# cloudy1.net
KiCad netlist of a schematic drawn in EAGLE
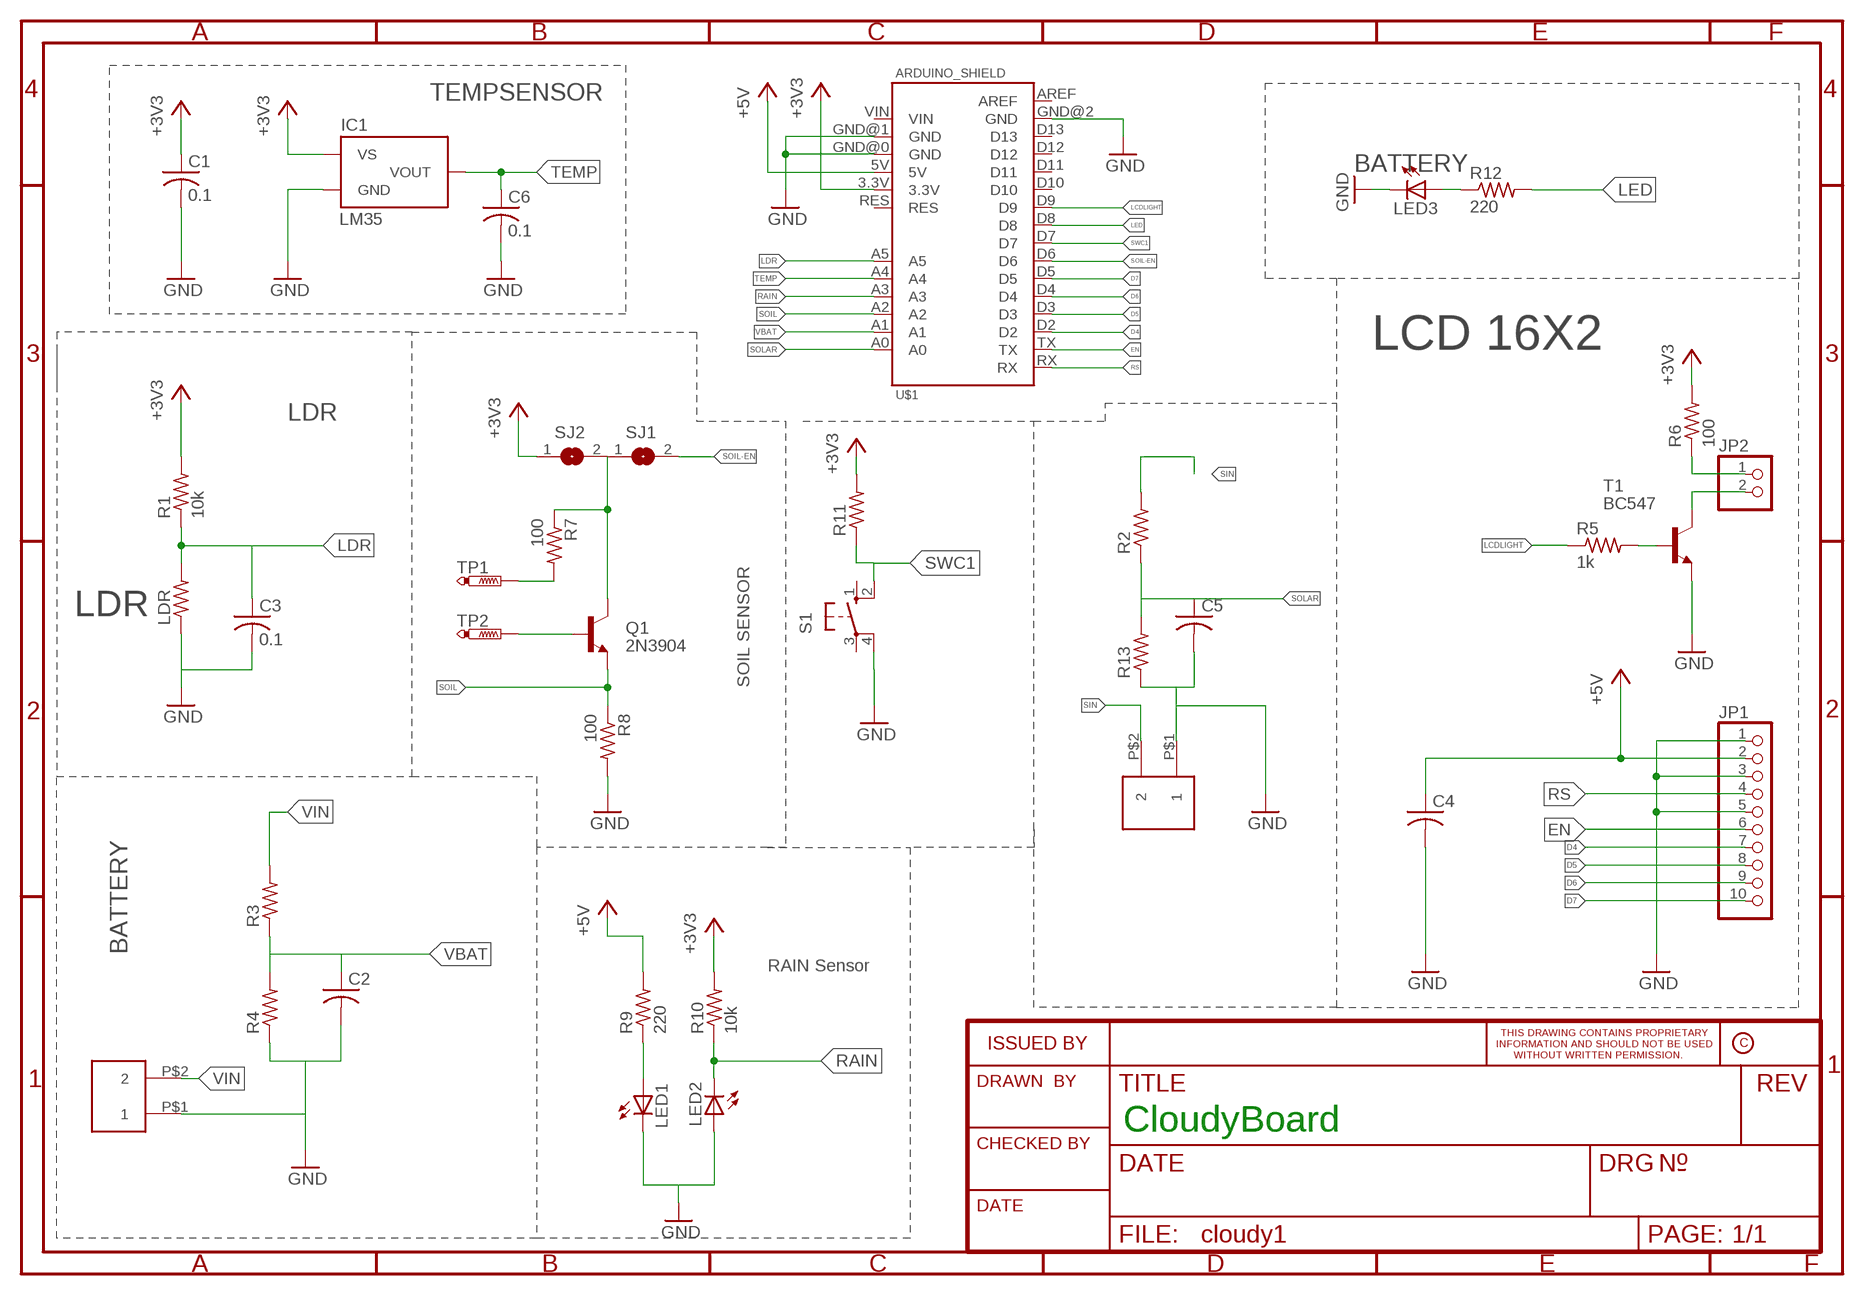
[diagram p0: schematic, sheet 1]

(export (version "E")
  (design (tool "Eeschema 10.0.6"))
  (components
    (comp (ref "C1")
      (value "0.1")
      (footprint "eagle-import:C0805")
      (libsource (lib "eagle-import") (part "C-USC0805"))
    )
    (comp (ref "C2")
      (value "C-USC0805")
      (footprint "eagle-import:C0805")
      (libsource (lib "eagle-import") (part "C-USC0805"))
    )
    (comp (ref "C3")
      (value "0.1")
      (footprint "eagle-import:C0805")
      (libsource (lib "eagle-import") (part "C-USC0805"))
    )
    (comp (ref "C4")
      (value "C-USC0805")
      (footprint "eagle-import:C0805")
      (libsource (lib "eagle-import") (part "C-USC0805"))
    )
    (comp (ref "C5")
      (value "C-USC0805")
      (footprint "eagle-import:C0805")
      (libsource (lib "eagle-import") (part "C-USC0805"))
    )
    (comp (ref "C6")
      (value "0.1")
      (footprint "eagle-import:C0805")
      (libsource (lib "eagle-import") (part "C-USC0805"))
    )
    (comp (ref "IC1")
      (value "LM35")
      (footprint "eagle-import:TO92")
      (libsource (lib "eagle-import") (part "LM35"))
    )
    (comp (ref "JP1")
      (value "PINHD-1X10")
      (footprint "eagle-import:1X10")
      (libsource (lib "eagle-import") (part "PINHD-1X10"))
    )
    (comp (ref "JP2")
      (value "PINHD-1X2")
      (footprint "eagle-import:1X02")
      (libsource (lib "eagle-import") (part "PINHD-1X2"))
    )
    (comp (ref "LDR")
      (value "R-US_0204/5")
      (footprint "eagle-import:0204_5")
      (libsource (lib "eagle-import") (part "R-US_0204/5"))
    )
    (comp (ref "LED1")
      (value "LED5MM")
      (footprint "eagle-import:LED5MM")
      (libsource (lib "eagle-import") (part "LED5MM"))
    )
    (comp (ref "LED2")
      (value "LED5MM")
      (footprint "eagle-import:LED5MM")
      (libsource (lib "eagle-import") (part "LED5MM"))
    )
    (comp (ref "LED3")
      (value "LED5MM")
      (footprint "eagle-import:LED5MM")
      (libsource (lib "eagle-import") (part "LED5MM"))
    )
    (comp (ref "Q1")
      (value "2N3904")
      (footprint "eagle-import:TO92")
      (libsource (lib "eagle-import") (part "2N3904"))
    )
    (comp (ref "R1")
      (value "10k")
      (footprint "eagle-import:0204_7")
      (libsource (lib "eagle-import") (part "R-US_0204/7"))
    )
    (comp (ref "R2")
      (value "R-US_0204/7")
      (footprint "eagle-import:0204_7")
      (libsource (lib "eagle-import") (part "R-US_0204/7"))
    )
    (comp (ref "R3")
      (value "R-US_0204/7")
      (footprint "eagle-import:0204_7")
      (libsource (lib "eagle-import") (part "R-US_0204/7"))
    )
    (comp (ref "R4")
      (value "R-US_0204/7")
      (footprint "eagle-import:0204_7")
      (libsource (lib "eagle-import") (part "R-US_0204/7"))
    )
    (comp (ref "R5")
      (value "1k")
      (footprint "eagle-import:0204_7")
      (libsource (lib "eagle-import") (part "R-US_0204/7"))
    )
    (comp (ref "R6")
      (value "100")
      (footprint "eagle-import:0204_7")
      (libsource (lib "eagle-import") (part "R-US_0204/7"))
    )
    (comp (ref "R7")
      (value "100")
      (footprint "eagle-import:R0805")
      (libsource (lib "eagle-import") (part "R-US_R0805"))
    )
    (comp (ref "R8")
      (value "100")
      (footprint "eagle-import:R0805")
      (libsource (lib "eagle-import") (part "R-US_R0805"))
    )
    (comp (ref "R9")
      (value "220")
      (footprint "eagle-import:0204_7")
      (libsource (lib "eagle-import") (part "R-US_0204/7"))
    )
    (comp (ref "R10")
      (value "10k")
      (footprint "eagle-import:0204_7")
      (libsource (lib "eagle-import") (part "R-US_0204/7"))
    )
    (comp (ref "R11")
      (value "R-US_0207/10")
      (footprint "eagle-import:0207_10")
      (libsource (lib "eagle-import") (part "R-US_0207/10"))
    )
    (comp (ref "R12")
      (value "220")
      (footprint "eagle-import:0204_7")
      (libsource (lib "eagle-import") (part "R-US_0204/7"))
    )
    (comp (ref "R13")
      (value "R-US_0204/7")
      (footprint "eagle-import:0204_7")
      (libsource (lib "eagle-import") (part "R-US_0204/7"))
    )
    (comp (ref "S1")
      (value "10-XX")
      (footprint "eagle-import:B3F-10XX")
      (libsource (lib "eagle-import") (part "10-XX"))
    )
    (comp (ref "SJ1") (value "SJ") (footprint "eagle-import:SJ") (libsource (lib "eagle-import") (part "SJ")))
    (comp (ref "SJ2") (value "SJ") (footprint "eagle-import:SJ") (libsource (lib "eagle-import") (part "SJ")))
    (comp (ref "T1")
      (value "BC547")
      (footprint "eagle-import:TO92")
      (libsource (lib "eagle-import") (part "BC547"))
    )
    (comp (ref "TP1")
      (value "PTR1TP19SQ")
      (footprint "eagle-import:TP19SQ")
      (libsource (lib "eagle-import") (part "PTR1TP19SQ"))
    )
    (comp (ref "TP2")
      (value "PTR1TP19SQ")
      (footprint "eagle-import:TP19SQ")
      (libsource (lib "eagle-import") (part "PTR1TP19SQ"))
    )
    (comp (ref "U$1")
      (value "ARDUINO_SHIELD")
      (footprint "eagle-import:ARDUINO_SHIELD")
      (libsource (lib "eagle-import") (part "ARDUINO_SHIELD"))
    )
    (comp (ref "U$2")
      (value "POWER_TERMINAL")
      (footprint "eagle-import:POWER_TERMINAL_2")
      (libsource (lib "eagle-import") (part "POWER_TERMINAL"))
    )
    (comp (ref "U$3")
      (value "POWER_TERMINAL")
      (footprint "eagle-import:POWER_TERMINAL_2")
      (libsource (lib "eagle-import") (part "POWER_TERMINAL"))
    )
  )
  (nets
    (net (code "1") (name "+3V3") (class "Default")
      (node (ref "C1") (pin "1") (pinfunction "1_1") (pintype "passive"))
      (node (ref "IC1") (pin "VS") (pinfunction "VS_VS") (pintype "passive"))
      (node (ref "R1") (pin "2") (pinfunction "2_2") (pintype "passive"))
      (node (ref "R10") (pin "2") (pinfunction "2_2") (pintype "passive"))
      (node (ref "R11") (pin "2") (pinfunction "2_2") (pintype "passive"))
      (node (ref "R6") (pin "2") (pinfunction "2_2") (pintype "passive"))
      (node (ref "SJ2") (pin "1") (pinfunction "1_1") (pintype "passive"))
      (node (ref "U$1") (pin "3.3V") (pinfunction "3.3V_3.3V") (pintype "passive"))
    )
    (net (code "2") (name "+5V") (class "Default")
      (node (ref "C4") (pin "1") (pinfunction "1_1") (pintype "passive"))
      (node (ref "JP1") (pin "2") (pinfunction "2_2") (pintype "passive"))
      (node (ref "R9") (pin "2") (pinfunction "2_2") (pintype "passive"))
      (node (ref "U$1") (pin "5V") (pinfunction "5V_5V") (pintype "passive"))
    )
    (net (code "3") (name "D4") (class "Default")
      (node (ref "JP1") (pin "7") (pinfunction "7_7") (pintype "passive"))
      (node (ref "U$1") (pin "D2") (pinfunction "D2_D2") (pintype "passive"))
    )
    (net (code "4") (name "D5") (class "Default")
      (node (ref "JP1") (pin "8") (pinfunction "8_8") (pintype "passive"))
      (node (ref "U$1") (pin "D3") (pinfunction "D3_D3") (pintype "passive"))
    )
    (net (code "5") (name "D6") (class "Default")
      (node (ref "JP1") (pin "9") (pinfunction "9_9") (pintype "passive"))
      (node (ref "U$1") (pin "D4") (pinfunction "D4_D4") (pintype "passive"))
    )
    (net (code "6") (name "D7") (class "Default")
      (node (ref "JP1") (pin "10") (pinfunction "10_10") (pintype "passive"))
      (node (ref "U$1") (pin "D5") (pinfunction "D5_D5") (pintype "passive"))
    )
    (net (code "7") (name "EN") (class "Default")
      (node (ref "JP1") (pin "6") (pinfunction "6_6") (pintype "passive"))
      (node (ref "U$1") (pin "TX") (pinfunction "TX_TX") (pintype "passive"))
    )
    (net (code "8") (name "GND") (class "Default")
      (node (ref "C1") (pin "2") (pinfunction "2_2") (pintype "passive"))
      (node (ref "C2") (pin "2") (pinfunction "2_2") (pintype "passive"))
      (node (ref "C3") (pin "2") (pinfunction "2_2") (pintype "passive"))
      (node (ref "C4") (pin "2") (pinfunction "2_2") (pintype "passive"))
      (node (ref "C5") (pin "2") (pinfunction "2_2") (pintype "passive"))
      (node (ref "C6") (pin "2") (pinfunction "2_2") (pintype "passive"))
      (node (ref "IC1") (pin "GND") (pinfunction "GND_GND") (pintype "passive"))
      (node (ref "JP1") (pin "1") (pinfunction "1_1") (pintype "passive"))
      (node (ref "JP1") (pin "3") (pinfunction "3_3") (pintype "passive"))
      (node (ref "JP1") (pin "5") (pinfunction "5_5") (pintype "passive"))
      (node (ref "LDR") (pin "1") (pinfunction "1_1") (pintype "passive"))
      (node (ref "LED1") (pin "K") (pinfunction "C_K") (pintype "passive"))
      (node (ref "LED2") (pin "A") (pinfunction "A_A") (pintype "passive"))
      (node (ref "LED3") (pin "K") (pinfunction "C_K") (pintype "passive"))
      (node (ref "R13") (pin "1") (pinfunction "1_1") (pintype "passive"))
      (node (ref "R4") (pin "1") (pinfunction "1_1") (pintype "passive"))
      (node (ref "R8") (pin "2") (pinfunction "2_2") (pintype "passive"))
      (node (ref "S1") (pin "4") (pinfunction "P1_4") (pintype "passive"))
      (node (ref "T1") (pin "1") (pinfunction "E_1") (pintype "passive"))
      (node (ref "U$1") (pin "GND@0") (pinfunction "GND_GND@0") (pintype "passive"))
      (node (ref "U$1") (pin "GND@1") (pinfunction "GND_GND@1") (pintype "passive"))
      (node (ref "U$1") (pin "GND@2") (pinfunction "GND_GND@2") (pintype "passive"))
      (node (ref "U$2") (pin "P$1") (pinfunction "1_P$1") (pintype "passive"))
      (node (ref "U$3") (pin "P$1") (pinfunction "1_P$1") (pintype "passive"))
    )
    (net (code "9") (name "LCDLIGHT") (class "Default")
      (node (ref "R5") (pin "1") (pinfunction "1_1") (pintype "passive"))
      (node (ref "U$1") (pin "D9") (pinfunction "D9_D9") (pintype "passive"))
    )
    (net (code "10") (name "LDR") (class "Default")
      (node (ref "C3") (pin "1") (pinfunction "1_1") (pintype "passive"))
      (node (ref "LDR") (pin "2") (pinfunction "2_2") (pintype "passive"))
      (node (ref "R1") (pin "1") (pinfunction "1_1") (pintype "passive"))
      (node (ref "U$1") (pin "A5") (pinfunction "A5_A5") (pintype "passive"))
    )
    (net (code "11") (name "LED") (class "Default")
      (node (ref "R12") (pin "2") (pinfunction "2_2") (pintype "passive"))
      (node (ref "U$1") (pin "D8") (pinfunction "D8_D8") (pintype "passive"))
    )
    (net (code "12") (name "Net-(JP2-Pad1)") (class "Default")
      (node (ref "JP2") (pin "1") (pinfunction "1_1") (pintype "passive"))
      (node (ref "R6") (pin "1") (pinfunction "1_1") (pintype "passive"))
    )
    (net (code "13") (name "Net-(LED1-PadA)") (class "Default")
      (node (ref "LED1") (pin "A") (pinfunction "A_A") (pintype "passive"))
      (node (ref "R9") (pin "1") (pinfunction "1_1") (pintype "passive"))
    )
    (net (code "14") (name "Net-(LED3-PadA)") (class "Default")
      (node (ref "LED3") (pin "A") (pinfunction "A_A") (pintype "passive"))
      (node (ref "R12") (pin "1") (pinfunction "1_1") (pintype "passive"))
    )
    (net (code "15") (name "Net-(Q1-B)") (class "Default")
      (node (ref "Q1") (pin "2") (pinfunction "B_2") (pintype "passive"))
      (node (ref "TP2") (pin "TP") (pinfunction "TP_TP") (pintype "input"))
    )
    (net (code "16") (name "Net-(Q1-C)") (class "Default")
      (node (ref "Q1") (pin "1") (pinfunction "C_1") (pintype "passive"))
      (node (ref "R7") (pin "1") (pinfunction "1_1") (pintype "passive"))
      (node (ref "SJ1") (pin "1") (pinfunction "1_1") (pintype "passive"))
      (node (ref "SJ2") (pin "2") (pinfunction "2_2") (pintype "passive"))
    )
    (net (code "17") (name "Net-(R7-Pad2)") (class "Default")
      (node (ref "R7") (pin "2") (pinfunction "2_2") (pintype "passive"))
      (node (ref "TP1") (pin "TP") (pinfunction "TP_TP") (pintype "input"))
    )
    (net (code "18") (name "Net-(T1-B)") (class "Default")
      (node (ref "R5") (pin "2") (pinfunction "2_2") (pintype "passive"))
      (node (ref "T1") (pin "2") (pinfunction "B_2") (pintype "passive"))
    )
    (net (code "19") (name "Net-(T1-C)") (class "Default")
      (node (ref "JP2") (pin "2") (pinfunction "2_2") (pintype "passive"))
      (node (ref "T1") (pin "3") (pinfunction "C_3") (pintype "passive"))
    )
    (net (code "20") (name "RAIN") (class "Default")
      (node (ref "LED2") (pin "K") (pinfunction "C_K") (pintype "passive"))
      (node (ref "R10") (pin "1") (pinfunction "1_1") (pintype "passive"))
      (node (ref "U$1") (pin "A3") (pinfunction "A3_A3") (pintype "passive"))
    )
    (net (code "21") (name "RS") (class "Default")
      (node (ref "JP1") (pin "4") (pinfunction "4_4") (pintype "passive"))
      (node (ref "U$1") (pin "RX") (pinfunction "RX_RX") (pintype "passive"))
    )
    (net (code "22") (name "SIN") (class "Default")
      (node (ref "R2") (pin "2") (pinfunction "2_2") (pintype "passive"))
      (node (ref "U$3") (pin "P$2") (pinfunction "2_P$2") (pintype "passive"))
    )
    (net (code "23") (name "SOIL") (class "Default")
      (node (ref "Q1") (pin "3") (pinfunction "E_3") (pintype "passive"))
      (node (ref "R8") (pin "1") (pinfunction "1_1") (pintype "passive"))
      (node (ref "U$1") (pin "A2") (pinfunction "A2_A2") (pintype "passive"))
    )
    (net (code "24") (name "SOIL-EN") (class "Default")
      (node (ref "SJ1") (pin "2") (pinfunction "2_2") (pintype "passive"))
      (node (ref "U$1") (pin "D6") (pinfunction "D6_D6") (pintype "passive"))
    )
    (net (code "25") (name "SOLAR") (class "Default")
      (node (ref "C5") (pin "1") (pinfunction "1_1") (pintype "passive"))
      (node (ref "R13") (pin "2") (pinfunction "2_2") (pintype "passive"))
      (node (ref "R2") (pin "1") (pinfunction "1_1") (pintype "passive"))
      (node (ref "U$1") (pin "A0") (pinfunction "A0_A0") (pintype "passive"))
    )
    (net (code "26") (name "SWC1") (class "Default")
      (node (ref "R11") (pin "1") (pinfunction "1_1") (pintype "passive"))
      (node (ref "S1") (pin "2") (pinfunction "S1_2") (pintype "passive"))
      (node (ref "U$1") (pin "D7") (pinfunction "D7_D7") (pintype "passive"))
    )
    (net (code "27") (name "TEMP") (class "Default")
      (node (ref "C6") (pin "1") (pinfunction "1_1") (pintype "passive"))
      (node (ref "IC1") (pin "VOUT") (pinfunction "VOUT_VOUT") (pintype "passive"))
      (node (ref "U$1") (pin "A4") (pinfunction "A4_A4") (pintype "passive"))
    )
    (net (code "28") (name "VBAT") (class "Default")
      (node (ref "C2") (pin "1") (pinfunction "1_1") (pintype "passive"))
      (node (ref "R3") (pin "1") (pinfunction "1_1") (pintype "passive"))
      (node (ref "R4") (pin "2") (pinfunction "2_2") (pintype "passive"))
      (node (ref "U$1") (pin "A1") (pinfunction "A1_A1") (pintype "passive"))
    )
    (net (code "29") (name "VIN") (class "Default")
      (node (ref "R3") (pin "2") (pinfunction "2_2") (pintype "passive"))
      (node (ref "U$2") (pin "P$2") (pinfunction "2_P$2") (pintype "passive"))
    )
    (net (code "30") (name "unconnected-(S1-P-Pad3)") (class "Default")
      (node (ref "S1") (pin "3") (pinfunction "P_3") (pintype "passive"))
    )
    (net (code "31") (name "unconnected-(S1-S-Pad1)") (class "Default")
      (node (ref "S1") (pin "1") (pinfunction "S_1") (pintype "passive"))
    )
    (net (code "32") (name "unconnected-(U$1-PadAREF)") (class "Default")
      (node (ref "U$1") (pin "AREF") (pinfunction "AREF_AREF") (pintype "passive"))
    )
    (net (code "33") (name "unconnected-(U$1-PadD10)") (class "Default")
      (node (ref "U$1") (pin "D10") (pinfunction "D10_D10") (pintype "passive"))
    )
    (net (code "34") (name "unconnected-(U$1-PadD11)") (class "Default")
      (node (ref "U$1") (pin "D11") (pinfunction "D11_D11") (pintype "passive"))
    )
    (net (code "35") (name "unconnected-(U$1-PadD12)") (class "Default")
      (node (ref "U$1") (pin "D12") (pinfunction "D12_D12") (pintype "passive"))
    )
    (net (code "36") (name "unconnected-(U$1-PadD13)") (class "Default")
      (node (ref "U$1") (pin "D13") (pinfunction "D13_D13") (pintype "passive"))
    )
    (net (code "37") (name "unconnected-(U$1-PadRES)") (class "Default")
      (node (ref "U$1") (pin "RES") (pinfunction "RES_RES") (pintype "passive"))
    )
    (net (code "38") (name "unconnected-(U$1-PadVIN)") (class "Default")
      (node (ref "U$1") (pin "VIN") (pinfunction "VIN_VIN") (pintype "passive"))
    )
  )
)
